# Load_HRD.net
KiCad netlist of a schematic drawn in Altium Designer
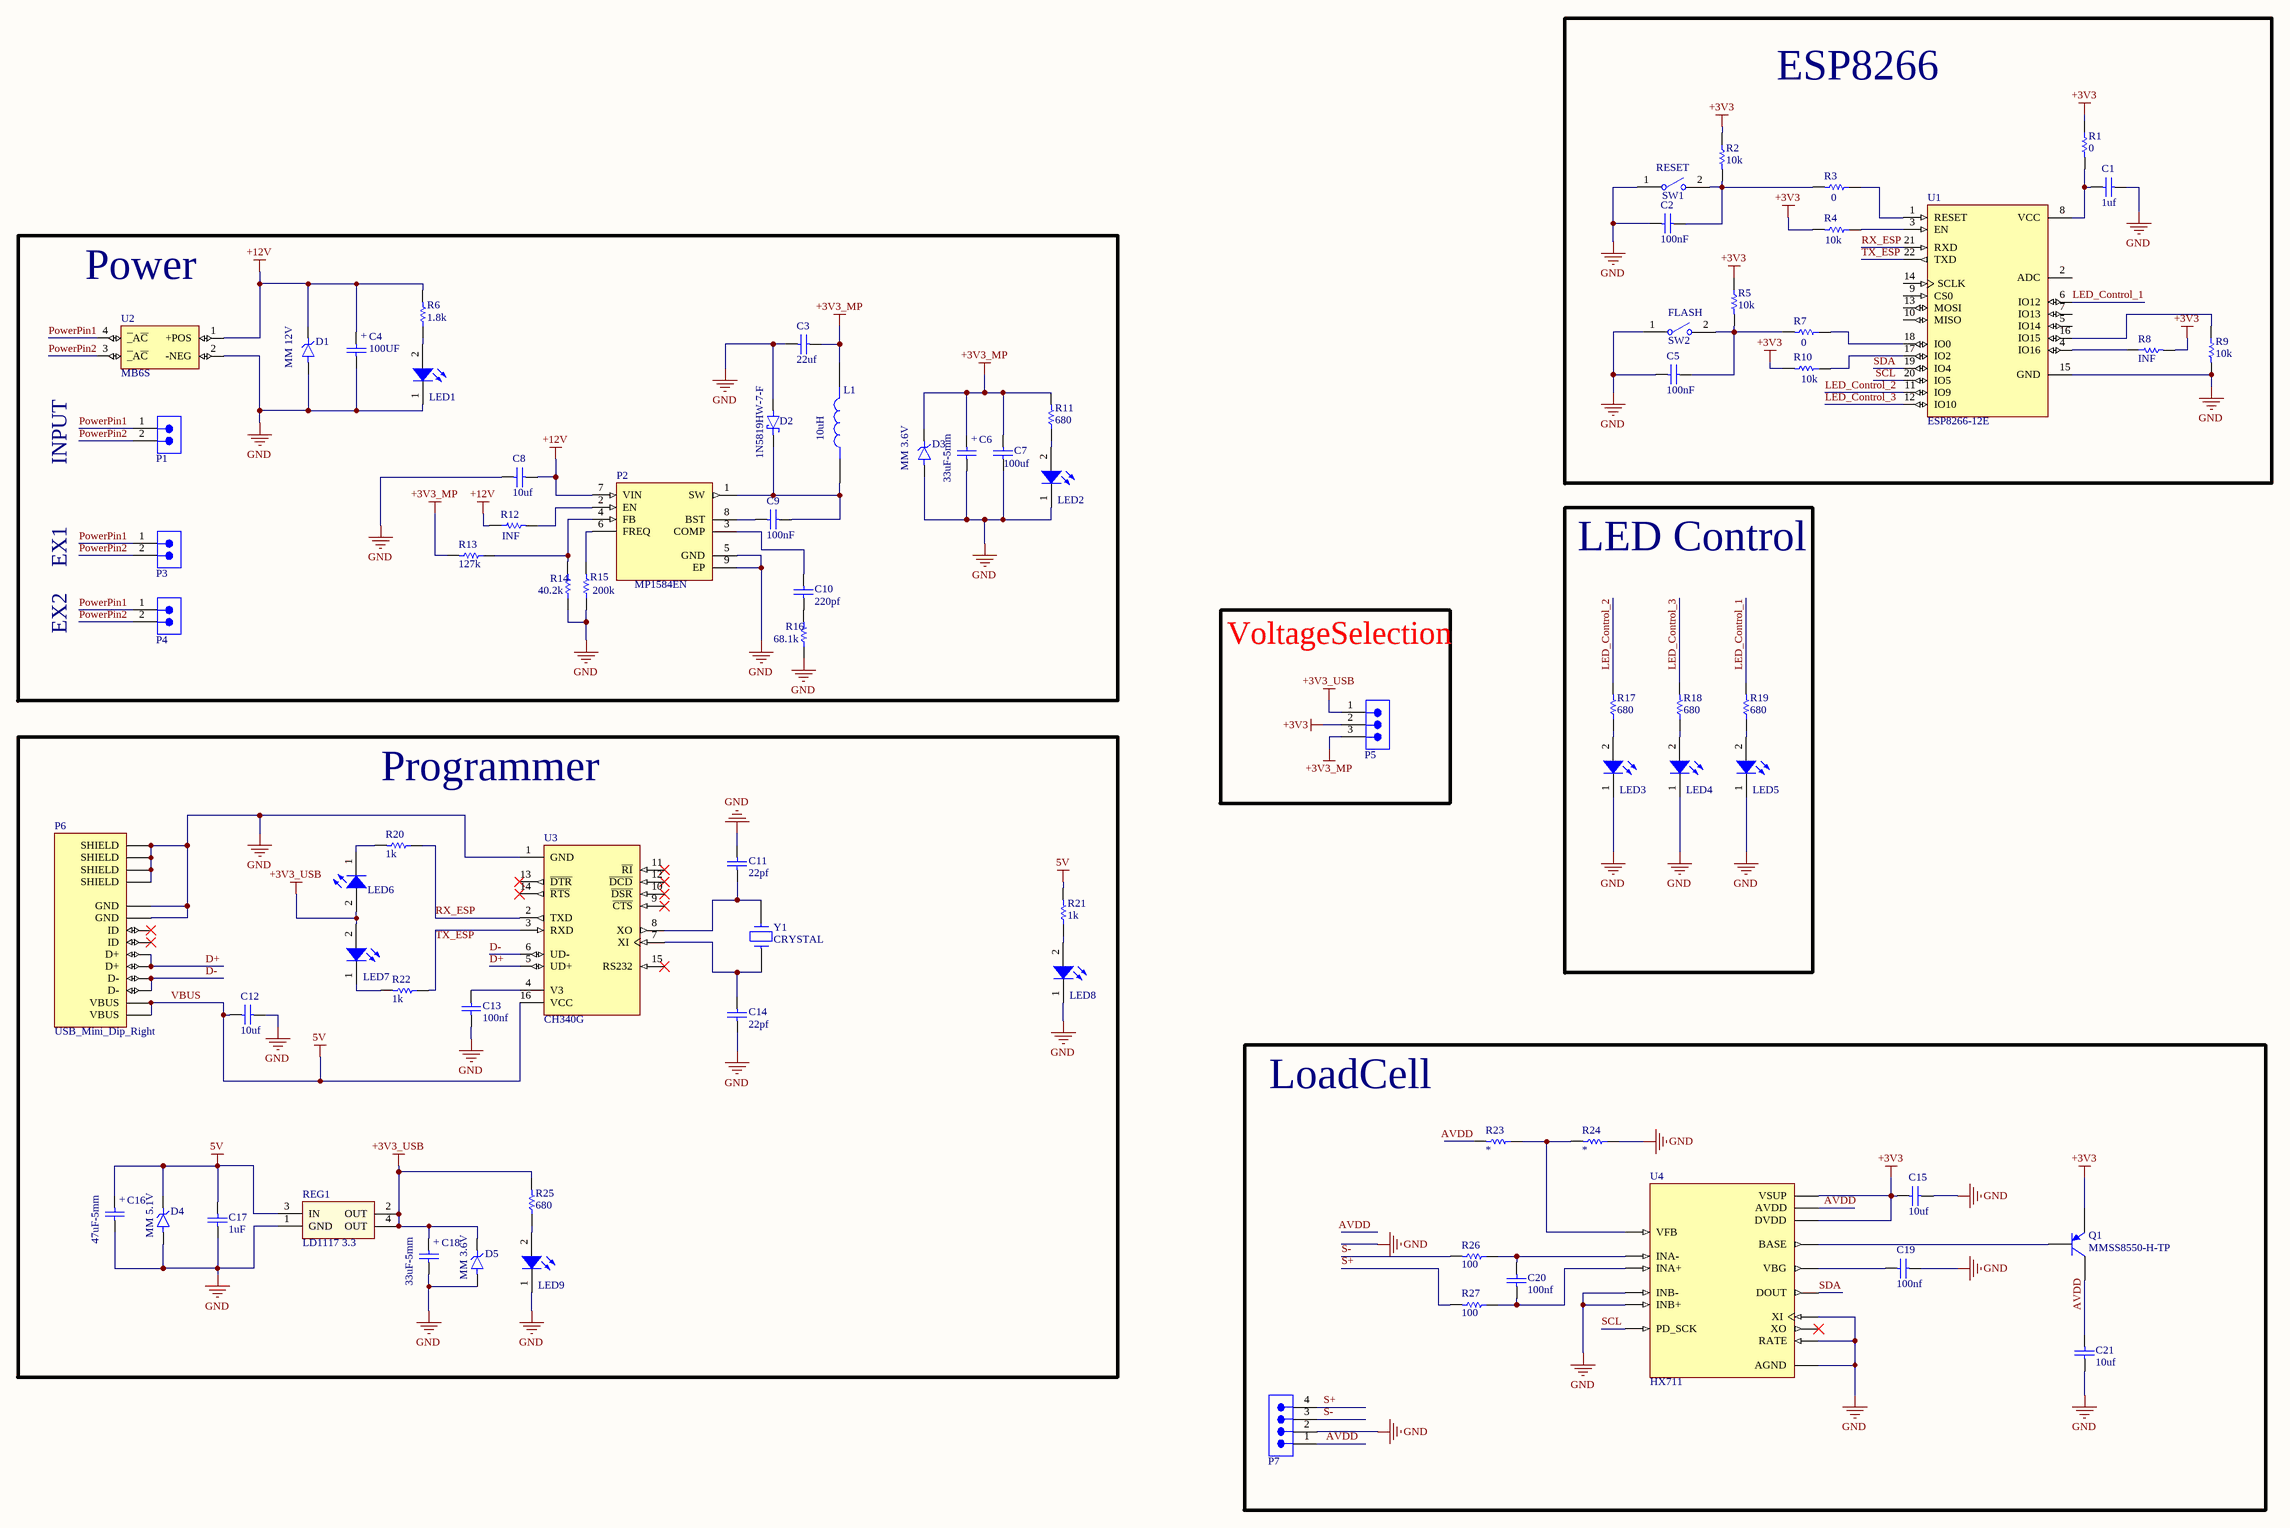
[diagram p0: Load_HRD.SchDoc]

(export (version "E")
  (design (tool "Eeschema 10.0.6"))
  (components
    (comp (ref "C1") (value "1uf") (footprint "SMD 805 CAP") (libsource (lib "MPA") (part "CAP B")))
    (comp (ref "C2") (value "100nF") (footprint "SMD 805 CAP") (libsource (lib "MPA") (part "CAP B")))
    (comp (ref "C3")
      (value "22uf")
      (footprint "SMD 805 CAP")
      (description "1uf")
      (libsource (lib "MPA") (part "CAP B"))
    )
    (comp (ref "C4")
      (value "100UF")
      (footprint "MY_CAP_POL 6MM")
      (description "CAP-3300Uf")
      (libsource (lib "MPA") (part "Cap Pol_6mm"))
    )
    (comp (ref "C5") (value "100nF") (footprint "SMD 805 CAP") (libsource (lib "MPA") (part "CAP B")))
    (comp (ref "C6")
      (value "33uF-5mm")
      (footprint "MY_CAP_POL 5MM")
      (description "CAP-3300Uf")
      (libsource (lib "MPA") (part "Cap Pol_5mm"))
    )
    (comp (ref "C7")
      (value "100uf")
      (footprint "SMD 805 CAP")
      (description "1uf")
      (libsource (lib "MPA") (part "CAP B"))
    )
    (comp (ref "C8")
      (value "10uf")
      (footprint "SMD 805 CAP")
      (description "1uf")
      (libsource (lib "MPA") (part "CAP B"))
    )
    (comp (ref "C9") (value "100nF") (footprint "SMD 805 CAP") (libsource (lib "MPA") (part "CAP B")))
    (comp (ref "C10")
      (value "220pf")
      (footprint "SMD 805 CAP")
      (description "1uf")
      (libsource (lib "MPA") (part "CAP B"))
    )
    (comp (ref "C11")
      (value "22pf")
      (footprint "SMD 805 CAP")
      (description "1uf")
      (libsource (lib "MPA") (part "CAP B"))
    )
    (comp (ref "C12")
      (value "10uf")
      (footprint "SMD 805 CAP")
      (description "1uf")
      (libsource (lib "MPA") (part "CAP B"))
    )
    (comp (ref "C13")
      (value "100nf")
      (footprint "SMD 805 CAP")
      (description "1uf")
      (libsource (lib "MPA") (part "CAP B"))
    )
    (comp (ref "C14")
      (value "22pf")
      (footprint "SMD 805 CAP")
      (description "1uf")
      (libsource (lib "MPA") (part "CAP B"))
    )
    (comp (ref "C15")
      (value "10uf")
      (footprint "SMD 805 CAP")
      (description "1uf")
      (libsource (lib "MPA") (part "CAP B"))
    )
    (comp (ref "C16")
      (value "47uF-5mm")
      (footprint "MY_CAP_POL 5MM")
      (description "CAP-3300Uf")
      (libsource (lib "MPA") (part "Cap Pol_5mm"))
    )
    (comp (ref "C17") (value "1uF") (footprint "SMD 805 CAP") (libsource (lib "MPA") (part "CAP B")))
    (comp (ref "C18")
      (value "33uF-5mm")
      (footprint "MY_CAP_POL 5MM")
      (description "CAP-3300Uf")
      (libsource (lib "MPA") (part "Cap Pol_5mm"))
    )
    (comp (ref "C19")
      (value "100nf")
      (footprint "SMD 805 CAP")
      (description "1uf")
      (libsource (lib "MPA") (part "CAP B"))
    )
    (comp (ref "C20")
      (value "100nf")
      (footprint "SMD 805 CAP")
      (description "1uf")
      (libsource (lib "MPA") (part "CAP B"))
    )
    (comp (ref "C21")
      (value "10uf")
      (footprint "SMD 805 CAP")
      (description "1uf")
      (libsource (lib "MPA") (part "CAP B"))
    )
    (comp (ref "D1")
      (value "MM 12V")
      (footprint "MiniMelf")
      (description "MiniMelf_500mW")
      (fields (field (name "MP") "ZM4736A_L0"))
      (libsource (lib "MPA") (part "MiniMelf_500mW"))
    )
    (comp (ref "D2")
      (value "1N5819HW-7-F")
      (footprint "1N5819HW-7-F")
      (libsource (lib "MPA") (part "1N5819HW-7-F"))
    )
    (comp (ref "D3")
      (value "MM 3.6V")
      (footprint "MiniMelf")
      (description "MiniMelf_500mW")
      (fields (field (name "MP") "ZM4736A_L0"))
      (libsource (lib "MPA") (part "MiniMelf_500mW"))
    )
    (comp (ref "D4")
      (value "MM 5.1V")
      (footprint "MiniMelf")
      (description "MiniMelf_500mW")
      (fields (field (name "MP") "ZM4736A_L0"))
      (libsource (lib "MPA") (part "MiniMelf_500mW"))
    )
    (comp (ref "D5")
      (value "MM 3.6V")
      (footprint "MiniMelf")
      (description "MiniMelf_500mW")
      (fields (field (name "MP") "ZM4736A_L0"))
      (libsource (lib "MPA") (part "MiniMelf_500mW"))
    )
    (comp (ref "L1")
      (value "10uH")
      (footprint "Inductor-4*4*3")
      (libsource (lib "MPA") (part "Inductor4*4*3"))
    )
    (comp (ref "LED1")
      (value "LED_SMD_0805")
      (footprint "LED_0805")
      (libsource (lib "MPA") (part "LED_SMD_0805"))
    )
    (comp (ref "LED2")
      (value "LED_SMD_0805")
      (footprint "LED_0805")
      (libsource (lib "MPA") (part "LED_SMD_0805"))
    )
    (comp (ref "LED3")
      (value "LED_SMD_0805")
      (footprint "LED_0805")
      (libsource (lib "MPA") (part "LED_SMD_0805"))
    )
    (comp (ref "LED4")
      (value "LED_SMD_0805")
      (footprint "LED_0805")
      (libsource (lib "MPA") (part "LED_SMD_0805"))
    )
    (comp (ref "LED5")
      (value "LED_SMD_0805")
      (footprint "LED_0805")
      (libsource (lib "MPA") (part "LED_SMD_0805"))
    )
    (comp (ref "LED6")
      (value "LED_SMD_0805")
      (footprint "LED_0805")
      (libsource (lib "MPA") (part "LED_SMD_0805"))
    )
    (comp (ref "LED7")
      (value "LED_SMD_0805")
      (footprint "LED_0805")
      (libsource (lib "MPA") (part "LED_SMD_0805"))
    )
    (comp (ref "LED8")
      (value "LED_SMD_0805")
      (footprint "LED_0805")
      (libsource (lib "MPA") (part "LED_SMD_0805"))
    )
    (comp (ref "LED9")
      (value "LED_SMD_0805")
      (footprint "LED_0805")
      (libsource (lib "MPA") (part "LED_SMD_0805"))
    )
    (comp (ref "P1")
      (value "691312510002")
      (footprint "691312510002")
      (description "WR-TBL Series 312 Open Horizontal PCB Header, THT, pitch 5.08mm, 2p")
      (fields (field (name "MANUFACTURER") "Wurth Elektronik"))
      (libsource (lib "Phonix5.08mm") (part "691312510002"))
    )
    (comp (ref "P2") (value "MP1584EN") (footprint "MP1584EN") (libsource (lib "MPA") (part "MP1584EN")))
    (comp (ref "P3")
      (value "691312510002")
      (footprint "691312510002")
      (description "WR-TBL Series 312 Open Horizontal PCB Header, THT, pitch 5.08mm, 2p")
      (fields (field (name "MANUFACTURER") "Wurth Elektronik"))
      (libsource (lib "Phonix5.08mm") (part "691312510002"))
    )
    (comp (ref "P4")
      (value "691312510002")
      (footprint "691312510002")
      (description "WR-TBL Series 312 Open Horizontal PCB Header, THT, pitch 5.08mm, 2p")
      (fields (field (name "MANUFACTURER") "Wurth Elektronik"))
      (libsource (lib "Phonix5.08mm") (part "691312510002"))
    )
    (comp (ref "P5")
      (value "61300311121")
      (footprint "61300311121")
      (description "WR-PHD Pin Header, THT, Vertical, pitch 2.54mm, 1 Row, 3P")
      (fields (field (name "MANUFACTURER") "Wurth Elektronik"))
      (libsource (lib "PinHeader") (part "61300311121"))
    )
    (comp (ref "P6")
      (value "USB_Mini_Dip_Right")
      (footprint "USB_MINI_Right")
      (libsource (lib "MPA") (part "USB_Mini_Dip_Right"))
    )
    (comp (ref "P7")
      (value "691312510004")
      (footprint "691312510004")
      (description "WR-TBL Series 312 Open Horizontal PCB Header, THT, pitch 5.08mm, 4p")
      (fields (field (name "MANUFACTURER") "Wurth Elektronik"))
      (libsource (lib "Phonix5.08mm") (part "691312510004"))
    )
    (comp (ref "Q1")
      (value "MMSS8550-H-TP")
      (footprint "MY_SMD_TRANSISTOR")
      (description "PNP 60V 625mW IC=200mA")
      (libsource (lib "MPA") (part "3906 SMD TRANSISTOR"))
    )
    (comp (ref "R1") (value "0") (footprint "SMD 805") (libsource (lib "MPA") (part "Resistor")))
    (comp (ref "R2") (value "10k") (footprint "SMD 805") (libsource (lib "MPA") (part "Resistor")))
    (comp (ref "R3") (value "0") (footprint "SMD 805") (libsource (lib "MPA") (part "Resistor")))
    (comp (ref "R4") (value "10k") (footprint "SMD 805") (libsource (lib "MPA") (part "Resistor")))
    (comp (ref "R5") (value "10k") (footprint "SMD 805") (libsource (lib "MPA") (part "Resistor")))
    (comp (ref "R6") (value "1.8k") (footprint "SMD 805") (libsource (lib "MPA") (part "Resistor")))
    (comp (ref "R7") (value "0") (footprint "SMD 805") (libsource (lib "MPA") (part "Resistor")))
    (comp (ref "R8") (value "INF") (footprint "SMD 805") (libsource (lib "MPA") (part "Resistor")))
    (comp (ref "R9") (value "10k") (footprint "SMD 805") (libsource (lib "MPA") (part "Resistor")))
    (comp (ref "R10") (value "10k") (footprint "SMD 805") (libsource (lib "MPA") (part "Resistor")))
    (comp (ref "R11") (value "680") (footprint "SMD 805") (libsource (lib "MPA") (part "Resistor")))
    (comp (ref "R12") (value "INF") (footprint "SMD 805") (libsource (lib "MPA") (part "Resistor")))
    (comp (ref "R13") (value "127k") (footprint "SMD 805") (libsource (lib "MPA") (part "Resistor")))
    (comp (ref "R14") (value "40.2k") (footprint "SMD 805") (libsource (lib "MPA") (part "Resistor")))
    (comp (ref "R15") (value "200k") (footprint "SMD 805") (libsource (lib "MPA") (part "Resistor")))
    (comp (ref "R16") (value "68.1k") (footprint "SMD 805") (libsource (lib "MPA") (part "Resistor")))
    (comp (ref "R17") (value "680") (footprint "SMD 805") (libsource (lib "MPA") (part "Resistor")))
    (comp (ref "R18") (value "680") (footprint "SMD 805") (libsource (lib "MPA") (part "Resistor")))
    (comp (ref "R19") (value "680") (footprint "SMD 805") (libsource (lib "MPA") (part "Resistor")))
    (comp (ref "R20") (value "1k") (footprint "SMD 805") (libsource (lib "MPA") (part "Resistor")))
    (comp (ref "R21") (value "1k") (footprint "SMD 805") (libsource (lib "MPA") (part "Resistor")))
    (comp (ref "R22") (value "1k") (footprint "SMD 805") (libsource (lib "MPA") (part "Resistor")))
    (comp (ref "R23") (value "*") (footprint "SMD 805") (libsource (lib "MPA") (part "Resistor")))
    (comp (ref "R24") (value "*") (footprint "SMD 805") (libsource (lib "MPA") (part "Resistor")))
    (comp (ref "R25") (value "680") (footprint "SMD 805") (libsource (lib "MPA") (part "Resistor")))
    (comp (ref "R26") (value "100") (footprint "SMD 805") (libsource (lib "MPA") (part "Resistor")))
    (comp (ref "R27") (value "100") (footprint "SMD 805") (libsource (lib "MPA") (part "Resistor")))
    (comp (ref "REG1")
      (value "LD1117 3.3")
      (footprint "MY_LD1117-3.3")
      (libsource (lib "MPA") (part "LD1117 3.3"))
    )
    (comp (ref "SW1")
      (value "434111043826")
      (footprint "WS-TASV_L6W3.5H4.3_4341x10438x6")
      (description "WS-TASV SMT Tact Switch, L6 x W3.5 x H4.3mm, 260g, SPST-NO, 12V, 50mA")
      (fields (field (name "MANUFACTURER") "Wurth Elektronik"))
      (libsource (lib "Altium_WS-TASV (rev22c)") (part "434111043826"))
    )
    (comp (ref "SW2")
      (value "434111043826")
      (footprint "WS-TASV_L6W3.5H4.3_4341x10438x6")
      (description "WS-TASV SMT Tact Switch, L6 x W3.5 x H4.3mm, 260g, SPST-NO, 12V, 50mA")
      (fields (field (name "MANUFACTURER") "Wurth Elektronik"))
      (libsource (lib "Altium_WS-TASV (rev22c)") (part "434111043826"))
    )
    (comp (ref "U1") (value "ESP8266-12E") (footprint "ESP8266") (libsource (lib "MPA") (part "ESP8266-12E")))
    (comp (ref "U2") (value "MB6S") (footprint "MB6S") (libsource (lib "MPA") (part "MB6S")))
    (comp (ref "U3") (value "CH340G") (footprint "CH340G") (libsource (lib "MPA") (part "CH340G")))
    (comp (ref "U4") (value "HX711") (footprint "HX711") (libsource (lib "MPA") (part "HX711")))
    (comp (ref "Y1")
      (value "CRYSTAL")
      (footprint "My_Crystal")
      (description "Crystal")
      (libsource (lib "MPA") (part "CRYSTAL"))
    )
  )
  (nets
    (net (code "1") (name "+3V3") (class "Default")
      (node (ref "C15") (pin "2") (pinfunction "2_2") (pintype "passive"))
      (node (ref "P5") (pin "2") (pinfunction "2_2") (pintype "passive"))
      (node (ref "Q1") (pin "E") (pinfunction "E_E") (pintype "passive"))
      (node (ref "R1") (pin "1") (pinfunction "1_1") (pintype "passive"))
      (node (ref "R10") (pin "2") (pinfunction "2_2") (pintype "passive"))
      (node (ref "R2") (pin "1") (pinfunction "1_1") (pintype "passive"))
      (node (ref "R4") (pin "2") (pinfunction "2_2") (pintype "passive"))
      (node (ref "R5") (pin "1") (pinfunction "1_1") (pintype "passive"))
      (node (ref "R8") (pin "2") (pinfunction "2_2") (pintype "passive"))
      (node (ref "U4") (pin "1") (pinfunction "VSUP_1") (pintype "power_in"))
      (node (ref "U4") (pin "16") (pinfunction "DVDD_16") (pintype "power_in"))
    )
    (net (code "2") (name "+3V3_MP") (class "Default")
      (node (ref "C3") (pin "2") (pinfunction "2_2") (pintype "passive"))
      (node (ref "C6") (pin "+") (pinfunction "+_+") (pintype "passive"))
      (node (ref "C7") (pin "2") (pinfunction "2_2") (pintype "passive"))
      (node (ref "D3") (pin "2") (pinfunction "2_2") (pintype "passive"))
      (node (ref "L1") (pin "2") (pinfunction "2_2") (pintype "passive"))
      (node (ref "P5") (pin "3") (pinfunction "3_3") (pintype "passive"))
      (node (ref "R11") (pin "2") (pinfunction "2_2") (pintype "passive"))
      (node (ref "R13") (pin "2") (pinfunction "2_2") (pintype "passive"))
    )
    (net (code "3") (name "+3V3_USB") (class "Default")
      (node (ref "C18") (pin "+") (pinfunction "+_+") (pintype "passive"))
      (node (ref "D5") (pin "2") (pinfunction "2_2") (pintype "passive"))
      (node (ref "LED6") (pin "2") (pinfunction "A_2") (pintype "passive"))
      (node (ref "LED7") (pin "2") (pinfunction "A_2") (pintype "passive"))
      (node (ref "P5") (pin "1") (pinfunction "1_1") (pintype "passive"))
      (node (ref "R25") (pin "2") (pinfunction "2_2") (pintype "passive"))
      (node (ref "REG1") (pin "2") (pinfunction "OUT_2") (pintype "power_in"))
      (node (ref "REG1") (pin "4") (pinfunction "OUT_4") (pintype "power_in"))
    )
    (net (code "4") (name "+12V") (class "Default")
      (node (ref "C4") (pin "+") (pinfunction "+_+") (pintype "passive"))
      (node (ref "C8") (pin "2") (pinfunction "2_2") (pintype "passive"))
      (node (ref "D1") (pin "2") (pinfunction "2_2") (pintype "passive"))
      (node (ref "P2") (pin "7") (pinfunction "VIN_7") (pintype "input"))
      (node (ref "R12") (pin "1") (pinfunction "1_1") (pintype "passive"))
      (node (ref "R6") (pin "2") (pinfunction "2_2") (pintype "passive"))
      (node (ref "U2") (pin "1") (pinfunction "+POS_1") (pintype "bidirectional"))
    )
    (net (code "5") (name "/AVDD") (class "Default")
      (node (ref "C21") (pin "1") (pinfunction "1_1") (pintype "passive"))
      (node (ref "P7") (pin "1") (pinfunction "1_1") (pintype "passive"))
      (node (ref "Q1") (pin "C") (pinfunction "C_C") (pintype "passive"))
      (node (ref "R23") (pin "2") (pinfunction "2_2") (pintype "passive"))
      (node (ref "U4") (pin "3") (pinfunction "AVDD_3") (pintype "power_in"))
    )
    (net (code "6") (name "/D+") (class "Default")
      (node (ref "P6") (pin "3") (pinfunction "D+_3") (pintype "bidirectional"))
      (node (ref "P6") (pin "8") (pinfunction "D+_8") (pintype "bidirectional"))
      (node (ref "U3") (pin "5") (pinfunction "UD+_5") (pintype "bidirectional"))
    )
    (net (code "7") (name "/D-") (class "Default")
      (node (ref "P6") (pin "2") (pinfunction "D-_2") (pintype "bidirectional"))
      (node (ref "P6") (pin "7") (pinfunction "D-_7") (pintype "bidirectional"))
      (node (ref "U3") (pin "6") (pinfunction "UD-_6") (pintype "bidirectional"))
    )
    (net (code "8") (name "/LED_Control_1") (class "Default")
      (node (ref "R19") (pin "2") (pinfunction "2_2") (pintype "passive"))
      (node (ref "U1") (pin "6") (pinfunction "IO12_6") (pintype "bidirectional"))
    )
    (net (code "9") (name "/LED_Control_2") (class "Default")
      (node (ref "R17") (pin "2") (pinfunction "2_2") (pintype "passive"))
      (node (ref "U1") (pin "11") (pinfunction "IO9_11") (pintype "bidirectional"))
    )
    (net (code "10") (name "/LED_Control_3") (class "Default")
      (node (ref "R18") (pin "2") (pinfunction "2_2") (pintype "passive"))
      (node (ref "U1") (pin "12") (pinfunction "IO10_12") (pintype "bidirectional"))
    )
    (net (code "11") (name "/PowerPin1") (class "Default")
      (node (ref "P1") (pin "1") (pinfunction "1_1") (pintype "passive"))
      (node (ref "P3") (pin "1") (pinfunction "1_1") (pintype "passive"))
      (node (ref "P4") (pin "1") (pinfunction "1_1") (pintype "passive"))
      (node (ref "U2") (pin "4") (pinfunction "~{_}A~{C}_4") (pintype "bidirectional"))
    )
    (net (code "12") (name "/PowerPin2") (class "Default")
      (node (ref "P1") (pin "2") (pinfunction "2_2") (pintype "passive"))
      (node (ref "P3") (pin "2") (pinfunction "2_2") (pintype "passive"))
      (node (ref "P4") (pin "2") (pinfunction "2_2") (pintype "passive"))
      (node (ref "U2") (pin "3") (pinfunction "~{_}A~{C}_3") (pintype "bidirectional"))
    )
    (net (code "13") (name "/RX_ESP") (class "Default")
      (node (ref "R20") (pin "1") (pinfunction "1_1") (pintype "passive"))
      (node (ref "U1") (pin "21") (pinfunction "RXD_21") (pintype "input"))
      (node (ref "U3") (pin "2") (pinfunction "TXD_2") (pintype "output"))
    )
    (net (code "14") (name "/S+") (class "Default")
      (node (ref "P7") (pin "4") (pinfunction "4_4") (pintype "passive"))
      (node (ref "R27") (pin "2") (pinfunction "2_2") (pintype "passive"))
    )
    (net (code "15") (name "/S-") (class "Default")
      (node (ref "P7") (pin "3") (pinfunction "3_3") (pintype "passive"))
      (node (ref "R26") (pin "2") (pinfunction "2_2") (pintype "passive"))
    )
    (net (code "16") (name "/SCL") (class "Default")
      (node (ref "U1") (pin "20") (pinfunction "IO5_20") (pintype "bidirectional"))
      (node (ref "U4") (pin "11") (pinfunction "PD_SCK_11") (pintype "input"))
    )
    (net (code "17") (name "/SDA") (class "Default")
      (node (ref "U1") (pin "19") (pinfunction "IO4_19") (pintype "bidirectional"))
      (node (ref "U4") (pin "12") (pinfunction "DOUT_12") (pintype "output"))
    )
    (net (code "18") (name "/TX_ESP") (class "Default")
      (node (ref "R22") (pin "1") (pinfunction "1_1") (pintype "passive"))
      (node (ref "U1") (pin "22") (pinfunction "TXD_22") (pintype "output"))
      (node (ref "U3") (pin "3") (pinfunction "RXD_3") (pintype "input"))
    )
    (net (code "19") (name "5V") (class "Default")
      (node (ref "C12") (pin "1") (pinfunction "1_1") (pintype "passive"))
      (node (ref "C16") (pin "+") (pinfunction "+_+") (pintype "passive"))
      (node (ref "C17") (pin "2") (pinfunction "2_2") (pintype "passive"))
      (node (ref "D4") (pin "2") (pinfunction "2_2") (pintype "passive"))
      (node (ref "P6") (pin "1") (pinfunction "VBUS_1") (pintype "power_in"))
      (node (ref "P6") (pin "6") (pinfunction "VBUS_6") (pintype "power_in"))
      (node (ref "R21") (pin "2") (pinfunction "2_2") (pintype "passive"))
      (node (ref "REG1") (pin "3") (pinfunction "IN_3") (pintype "power_in"))
      (node (ref "U3") (pin "16") (pinfunction "VCC_16") (pintype "power_in"))
    )
    (net (code "20") (name "GND") (class "Default")
      (node (ref "C1") (pin "2") (pinfunction "2_2") (pintype "passive"))
      (node (ref "C11") (pin "2") (pinfunction "2_2") (pintype "passive"))
      (node (ref "C12") (pin "2") (pinfunction "2_2") (pintype "passive"))
      (node (ref "C13") (pin "1") (pinfunction "1_1") (pintype "passive"))
      (node (ref "C14") (pin "1") (pinfunction "1_1") (pintype "passive"))
      (node (ref "C15") (pin "1") (pinfunction "1_1") (pintype "passive"))
      (node (ref "C16") (pin "-") (pinfunction "-_-") (pintype "passive"))
      (node (ref "C17") (pin "1") (pinfunction "1_1") (pintype "passive"))
      (node (ref "C18") (pin "-") (pinfunction "-_-") (pintype "passive"))
      (node (ref "C19") (pin "1") (pinfunction "1_1") (pintype "passive"))
      (node (ref "C2") (pin "2") (pinfunction "2_2") (pintype "passive"))
      (node (ref "C21") (pin "2") (pinfunction "2_2") (pintype "passive"))
      (node (ref "C3") (pin "1") (pinfunction "1_1") (pintype "passive"))
      (node (ref "C4") (pin "-") (pinfunction "-_-") (pintype "passive"))
      (node (ref "C5") (pin "2") (pinfunction "2_2") (pintype "passive"))
      (node (ref "C6") (pin "-") (pinfunction "-_-") (pintype "passive"))
      (node (ref "C7") (pin "1") (pinfunction "1_1") (pintype "passive"))
      (node (ref "C8") (pin "1") (pinfunction "1_1") (pintype "passive"))
      (node (ref "D1") (pin "1") (pinfunction "1_1") (pintype "passive"))
      (node (ref "D2") (pin "A") (pinfunction "A_A") (pintype "passive"))
      (node (ref "D3") (pin "1") (pinfunction "1_1") (pintype "passive"))
      (node (ref "D4") (pin "1") (pinfunction "1_1") (pintype "passive"))
      (node (ref "D5") (pin "1") (pinfunction "1_1") (pintype "passive"))
      (node (ref "LED1") (pin "1") (pinfunction "K_1") (pintype "passive"))
      (node (ref "LED2") (pin "1") (pinfunction "K_1") (pintype "passive"))
      (node (ref "LED3") (pin "1") (pinfunction "K_1") (pintype "passive"))
      (node (ref "LED4") (pin "1") (pinfunction "K_1") (pintype "passive"))
      (node (ref "LED5") (pin "1") (pinfunction "K_1") (pintype "passive"))
      (node (ref "LED8") (pin "1") (pinfunction "K_1") (pintype "passive"))
      (node (ref "LED9") (pin "1") (pinfunction "K_1") (pintype "passive"))
      (node (ref "P2") (pin "5") (pinfunction "GND_5") (pintype "power_in"))
      (node (ref "P2") (pin "9") (pinfunction "EP_9") (pintype "power_in"))
      (node (ref "P6") (pin "10") (pinfunction "GND_10") (pintype "power_in"))
      (node (ref "P6") (pin "11") (pinfunction "SHIELD_11") (pintype "passive"))
      (node (ref "P6") (pin "12") (pinfunction "SHIELD_12") (pintype "passive"))
      (node (ref "P6") (pin "5") (pinfunction "GND_5") (pintype "power_in"))
      (node (ref "P6") (pin "S1") (pinfunction "SHIELD_S1") (pintype "passive"))
      (node (ref "P6") (pin "S2") (pinfunction "SHIELD_S2") (pintype "passive"))
      (node (ref "P7") (pin "2") (pinfunction "2_2") (pintype "passive"))
      (node (ref "R14") (pin "1") (pinfunction "1_1") (pintype "passive"))
      (node (ref "R15") (pin "1") (pinfunction "1_1") (pintype "passive"))
      (node (ref "R16") (pin "1") (pinfunction "1_1") (pintype "passive"))
      (node (ref "R24") (pin "1") (pinfunction "1_1") (pintype "passive"))
      (node (ref "R9") (pin "2") (pinfunction "2_2") (pintype "passive"))
      (node (ref "REG1") (pin "1") (pinfunction "GND_1") (pintype "power_in"))
      (node (ref "SW1") (pin "1") (pinfunction "1_1") (pintype "passive"))
      (node (ref "SW2") (pin "1") (pinfunction "1_1") (pintype "passive"))
      (node (ref "U1") (pin "15") (pinfunction "GND_15") (pintype "power_in"))
      (node (ref "U2") (pin "2") (pinfunction "-NEG_2") (pintype "bidirectional"))
      (node (ref "U3") (pin "1") (pinfunction "GND_1") (pintype "power_in"))
      (node (ref "U4") (pin "10") (pinfunction "INB+_10") (pintype "input"))
      (node (ref "U4") (pin "14") (pinfunction "XI_14") (pintype "input"))
      (node (ref "U4") (pin "15") (pinfunction "RATE_15") (pintype "input"))
      (node (ref "U4") (pin "5") (pinfunction "AGND_5") (pintype "power_in"))
      (node (ref "U4") (pin "9") (pinfunction "INB-_9") (pintype "input"))
    )
    (net (code "21") (name "Net-(C2-Pad1)") (class "Default")
      (node (ref "C2") (pin "1") (pinfunction "1_1") (pintype "passive"))
      (node (ref "R2") (pin "2") (pinfunction "2_2") (pintype "passive"))
      (node (ref "R3") (pin "2") (pinfunction "2_2") (pintype "passive"))
      (node (ref "SW1") (pin "2") (pinfunction "2_2") (pintype "passive"))
    )
    (net (code "22") (name "Net-(C5-Pad1)") (class "Default")
      (node (ref "C5") (pin "1") (pinfunction "1_1") (pintype "passive"))
      (node (ref "R5") (pin "2") (pinfunction "2_2") (pintype "passive"))
      (node (ref "R7") (pin "2") (pinfunction "2_2") (pintype "passive"))
      (node (ref "SW2") (pin "2") (pinfunction "2_2") (pintype "passive"))
    )
    (net (code "23") (name "Net-(C10-Pad2)") (class "Default")
      (node (ref "C10") (pin "2") (pinfunction "2_2") (pintype "passive"))
      (node (ref "R16") (pin "2") (pinfunction "2_2") (pintype "passive"))
    )
    (net (code "24") (name "Net-(D2-K)") (class "Default")
      (node (ref "C9") (pin "2") (pinfunction "2_2") (pintype "passive"))
      (node (ref "D2") (pin "C") (pinfunction "K_C") (pintype "passive"))
      (node (ref "L1") (pin "1") (pinfunction "1_1") (pintype "passive"))
      (node (ref "P2") (pin "1") (pinfunction "SW_1") (pintype "output"))
    )
    (net (code "25") (name "Net-(LED1-A)") (class "Default")
      (node (ref "LED1") (pin "2") (pinfunction "A_2") (pintype "passive"))
      (node (ref "R6") (pin "1") (pinfunction "1_1") (pintype "passive"))
    )
    (net (code "26") (name "Net-(LED2-A)") (class "Default")
      (node (ref "LED2") (pin "2") (pinfunction "A_2") (pintype "passive"))
      (node (ref "R11") (pin "1") (pinfunction "1_1") (pintype "passive"))
    )
    (net (code "27") (name "Net-(LED3-A)") (class "Default")
      (node (ref "LED3") (pin "2") (pinfunction "A_2") (pintype "passive"))
      (node (ref "R17") (pin "1") (pinfunction "1_1") (pintype "passive"))
    )
    (net (code "28") (name "Net-(LED4-A)") (class "Default")
      (node (ref "LED4") (pin "2") (pinfunction "A_2") (pintype "passive"))
      (node (ref "R18") (pin "1") (pinfunction "1_1") (pintype "passive"))
    )
    (net (code "29") (name "Net-(LED5-A)") (class "Default")
      (node (ref "LED5") (pin "2") (pinfunction "A_2") (pintype "passive"))
      (node (ref "R19") (pin "1") (pinfunction "1_1") (pintype "passive"))
    )
    (net (code "30") (name "Net-(LED6-K)") (class "Default")
      (node (ref "LED6") (pin "1") (pinfunction "K_1") (pintype "passive"))
      (node (ref "R20") (pin "2") (pinfunction "2_2") (pintype "passive"))
    )
    (net (code "31") (name "Net-(LED7-K)") (class "Default")
      (node (ref "LED7") (pin "1") (pinfunction "K_1") (pintype "passive"))
      (node (ref "R22") (pin "2") (pinfunction "2_2") (pintype "passive"))
    )
    (net (code "32") (name "Net-(LED8-A)") (class "Default")
      (node (ref "LED8") (pin "2") (pinfunction "A_2") (pintype "passive"))
      (node (ref "R21") (pin "1") (pinfunction "1_1") (pintype "passive"))
    )
    (net (code "33") (name "Net-(LED9-A)") (class "Default")
      (node (ref "LED9") (pin "2") (pinfunction "A_2") (pintype "passive"))
      (node (ref "R25") (pin "1") (pinfunction "1_1") (pintype "passive"))
    )
    (net (code "34") (name "Net-(P2-BST)") (class "Default")
      (node (ref "C9") (pin "1") (pinfunction "1_1") (pintype "passive"))
      (node (ref "P2") (pin "8") (pinfunction "BST_8") (pintype "passive"))
    )
    (net (code "35") (name "Net-(P2-COMP)") (class "Default")
      (node (ref "C10") (pin "1") (pinfunction "1_1") (pintype "passive"))
      (node (ref "P2") (pin "3") (pinfunction "COMP_3") (pintype "passive"))
    )
    (net (code "36") (name "Net-(P2-EN)") (class "Default")
      (node (ref "P2") (pin "2") (pinfunction "EN_2") (pintype "input"))
      (node (ref "R12") (pin "2") (pinfunction "2_2") (pintype "passive"))
    )
    (net (code "37") (name "Net-(P2-FB)") (class "Default")
      (node (ref "P2") (pin "4") (pinfunction "FB_4") (pintype "input"))
      (node (ref "R13") (pin "1") (pinfunction "1_1") (pintype "passive"))
      (node (ref "R14") (pin "2") (pinfunction "2_2") (pintype "passive"))
    )
    (net (code "38") (name "Net-(P2-FREQ)") (class "Default")
      (node (ref "P2") (pin "6") (pinfunction "FREQ_6") (pintype "passive"))
      (node (ref "R15") (pin "2") (pinfunction "2_2") (pintype "passive"))
    )
    (net (code "39") (name "Net-(U1-EN)") (class "Default")
      (node (ref "R4") (pin "1") (pinfunction "1_1") (pintype "passive"))
      (node (ref "U1") (pin "3") (pinfunction "EN_3") (pintype "input"))
    )
    (net (code "40") (name "Net-(U1-IO0)") (class "Default")
      (node (ref "R7") (pin "1") (pinfunction "1_1") (pintype "passive"))
      (node (ref "U1") (pin "18") (pinfunction "IO0_18") (pintype "bidirectional"))
    )
    (net (code "41") (name "Net-(U1-IO2)") (class "Default")
      (node (ref "R10") (pin "1") (pinfunction "1_1") (pintype "passive"))
      (node (ref "U1") (pin "17") (pinfunction "IO2_17") (pintype "bidirectional"))
    )
    (net (code "42") (name "Net-(U1-IO15)") (class "Default")
      (node (ref "R9") (pin "1") (pinfunction "1_1") (pintype "passive"))
      (node (ref "U1") (pin "16") (pinfunction "IO15_16") (pintype "bidirectional"))
    )
    (net (code "43") (name "Net-(U1-IO16)") (class "Default")
      (node (ref "R8") (pin "1") (pinfunction "1_1") (pintype "passive"))
      (node (ref "U1") (pin "4") (pinfunction "IO16_4") (pintype "bidirectional"))
    )
    (net (code "44") (name "Net-(U1-RESET)") (class "Default")
      (node (ref "R3") (pin "1") (pinfunction "1_1") (pintype "passive"))
      (node (ref "U1") (pin "1") (pinfunction "RESET_1") (pintype "input"))
    )
    (net (code "45") (name "Net-(U1-VCC)") (class "Default")
      (node (ref "C1") (pin "1") (pinfunction "1_1") (pintype "passive"))
      (node (ref "R1") (pin "2") (pinfunction "2_2") (pintype "passive"))
      (node (ref "U1") (pin "8") (pinfunction "VCC_8") (pintype "power_in"))
    )
    (net (code "46") (name "Net-(U3-V3)") (class "Default")
      (node (ref "C13") (pin "2") (pinfunction "2_2") (pintype "passive"))
      (node (ref "U3") (pin "4") (pinfunction "V3_4") (pintype "power_in"))
    )
    (net (code "47") (name "Net-(U3-XI)") (class "Default")
      (node (ref "C14") (pin "2") (pinfunction "2_2") (pintype "passive"))
      (node (ref "U3") (pin "7") (pinfunction "XI_7") (pintype "input"))
      (node (ref "Y1") (pin "1") (pinfunction "1_1") (pintype "passive"))
    )
    (net (code "48") (name "Net-(U3-XO)") (class "Default")
      (node (ref "C11") (pin "1") (pinfunction "1_1") (pintype "passive"))
      (node (ref "U3") (pin "8") (pinfunction "XO_8") (pintype "output"))
      (node (ref "Y1") (pin "2") (pinfunction "2_2") (pintype "passive"))
    )
    (net (code "49") (name "Net-(U4-BASE)") (class "Default")
      (node (ref "Q1") (pin "B") (pinfunction "B_B") (pintype "passive"))
      (node (ref "U4") (pin "2") (pinfunction "BASE_2") (pintype "output"))
    )
    (net (code "50") (name "Net-(U4-INA+)") (class "Default")
      (node (ref "C20") (pin "1") (pinfunction "1_1") (pintype "passive"))
      (node (ref "R27") (pin "1") (pinfunction "1_1") (pintype "passive"))
      (node (ref "U4") (pin "8") (pinfunction "INA+_8") (pintype "input"))
    )
    (net (code "51") (name "Net-(U4-INA-)") (class "Default")
      (node (ref "C20") (pin "2") (pinfunction "2_2") (pintype "passive"))
      (node (ref "R26") (pin "1") (pinfunction "1_1") (pintype "passive"))
      (node (ref "U4") (pin "7") (pinfunction "INA-_7") (pintype "input"))
    )
    (net (code "52") (name "Net-(U4-VBG)") (class "Default")
      (node (ref "C19") (pin "2") (pinfunction "2_2") (pintype "passive"))
      (node (ref "U4") (pin "6") (pinfunction "VBG_6") (pintype "output"))
    )
    (net (code "53") (name "Net-(U4-VFB)") (class "Default")
      (node (ref "R23") (pin "1") (pinfunction "1_1") (pintype "passive"))
      (node (ref "R24") (pin "2") (pinfunction "2_2") (pintype "passive"))
      (node (ref "U4") (pin "4") (pinfunction "VFB_4") (pintype "input"))
    )
    (net (code "54") (name "unconnected-(P6-ID-Pad4)") (class "Default")
      (node (ref "P6") (pin "4") (pinfunction "ID_4") (pintype "bidirectional+no_connect"))
    )
    (net (code "55") (name "unconnected-(P6-ID-Pad9)") (class "Default")
      (node (ref "P6") (pin "9") (pinfunction "ID_9") (pintype "bidirectional+no_connect"))
    )
    (net (code "56") (name "unconnected-(U1-ADC-Pad2)") (class "Default")
      (node (ref "U1") (pin "2") (pinfunction "ADC_2") (pintype "passive"))
    )
    (net (code "57") (name "unconnected-(U1-CS0-Pad9)") (class "Default")
      (node (ref "U1") (pin "9") (pinfunction "CS0_9") (pintype "input"))
    )
    (net (code "58") (name "unconnected-(U1-IO13-Pad7)") (class "Default")
      (node (ref "U1") (pin "7") (pinfunction "IO13_7") (pintype "bidirectional"))
    )
    (net (code "59") (name "unconnected-(U1-IO14-Pad5)") (class "Default")
      (node (ref "U1") (pin "5") (pinfunction "IO14_5") (pintype "bidirectional"))
    )
    (net (code "60") (name "unconnected-(U1-MISO-Pad10)") (class "Default")
      (node (ref "U1") (pin "10") (pinfunction "MISO_10") (pintype "bidirectional"))
    )
    (net (code "61") (name "unconnected-(U1-MOSI-Pad13)") (class "Default")
      (node (ref "U1") (pin "13") (pinfunction "MOSI_13") (pintype "bidirectional"))
    )
    (net (code "62") (name "unconnected-(U1-SCLK-Pad14)") (class "Default")
      (node (ref "U1") (pin "14") (pinfunction "SCLK_14") (pintype "input"))
    )
    (net (code "63") (name "unconnected-(U3-RS232-Pad15)") (class "Default")
      (node (ref "U3") (pin "15") (pinfunction "RS232_15") (pintype "input+no_connect"))
    )
    (net (code "64") (name "unconnected-(U3-~{CTS}-Pad9)") (class "Default")
      (node (ref "U3") (pin "9") (pinfunction "~{CTS}_9") (pintype "input+no_connect"))
    )
    (net (code "65") (name "unconnected-(U3-~{DCD}-Pad12)") (class "Default")
      (node (ref "U3") (pin "12") (pinfunction "~{DCD}_12") (pintype "input+no_connect"))
    )
    (net (code "66") (name "unconnected-(U3-~{DSR}-Pad10)") (class "Default")
      (node (ref "U3") (pin "10") (pinfunction "~{DSR}_10") (pintype "input+no_connect"))
    )
    (net (code "67") (name "unconnected-(U3-~{DTR}-Pad13)") (class "Default")
      (node (ref "U3") (pin "13") (pinfunction "~{DTR}_13") (pintype "output+no_connect"))
    )
    (net (code "68") (name "unconnected-(U3-~{RI}-Pad11)") (class "Default")
      (node (ref "U3") (pin "11") (pinfunction "~{RI}_11") (pintype "input+no_connect"))
    )
    (net (code "69") (name "unconnected-(U3-~{RTS}-Pad14)") (class "Default")
      (node (ref "U3") (pin "14") (pinfunction "~{RTS}_14") (pintype "output+no_connect"))
    )
    (net (code "70") (name "unconnected-(U4-XO-Pad13)") (class "Default")
      (node (ref "U4") (pin "13") (pinfunction "XO_13") (pintype "output+no_connect"))
    )
  )
)
